# mainboard.net
KiCad netlist of a schematic drawn in EAGLE
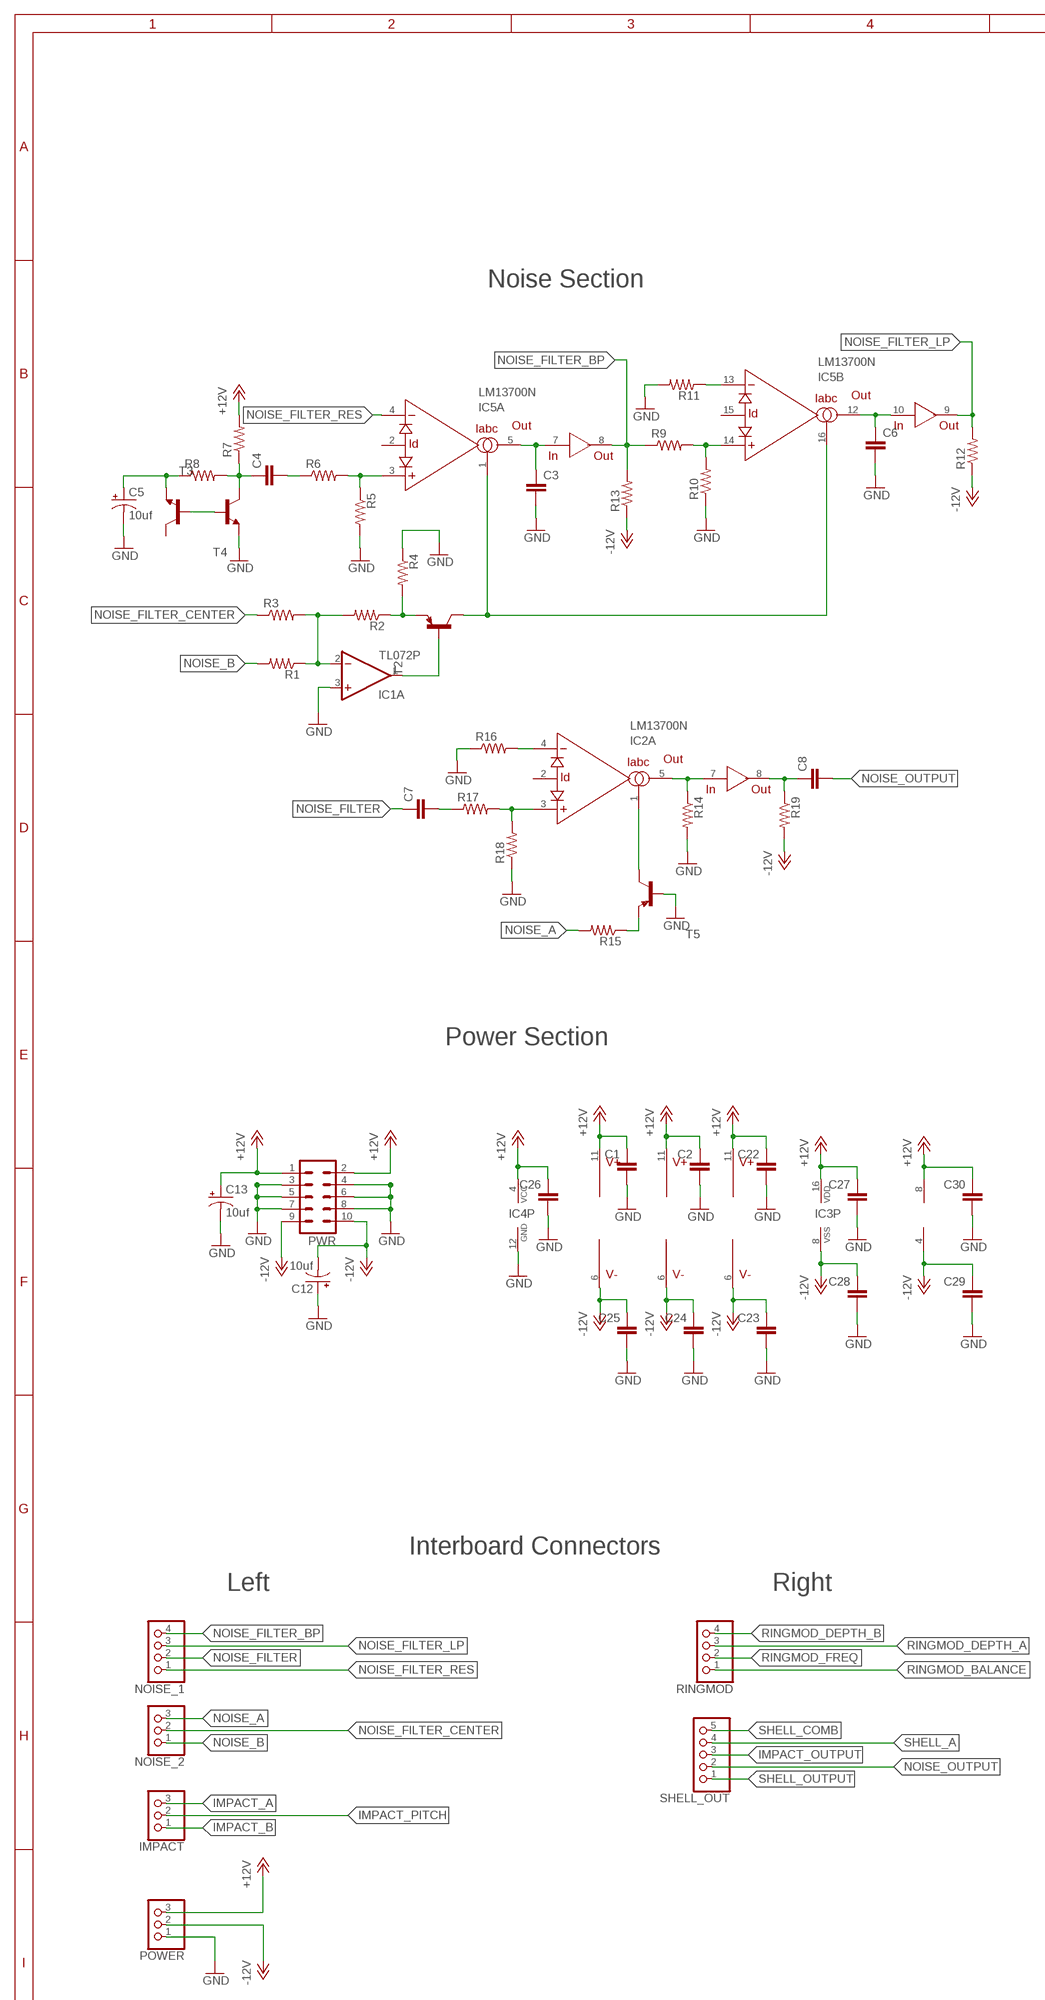
[diagram p0: schematic, sheet 1, part 1 of 2]
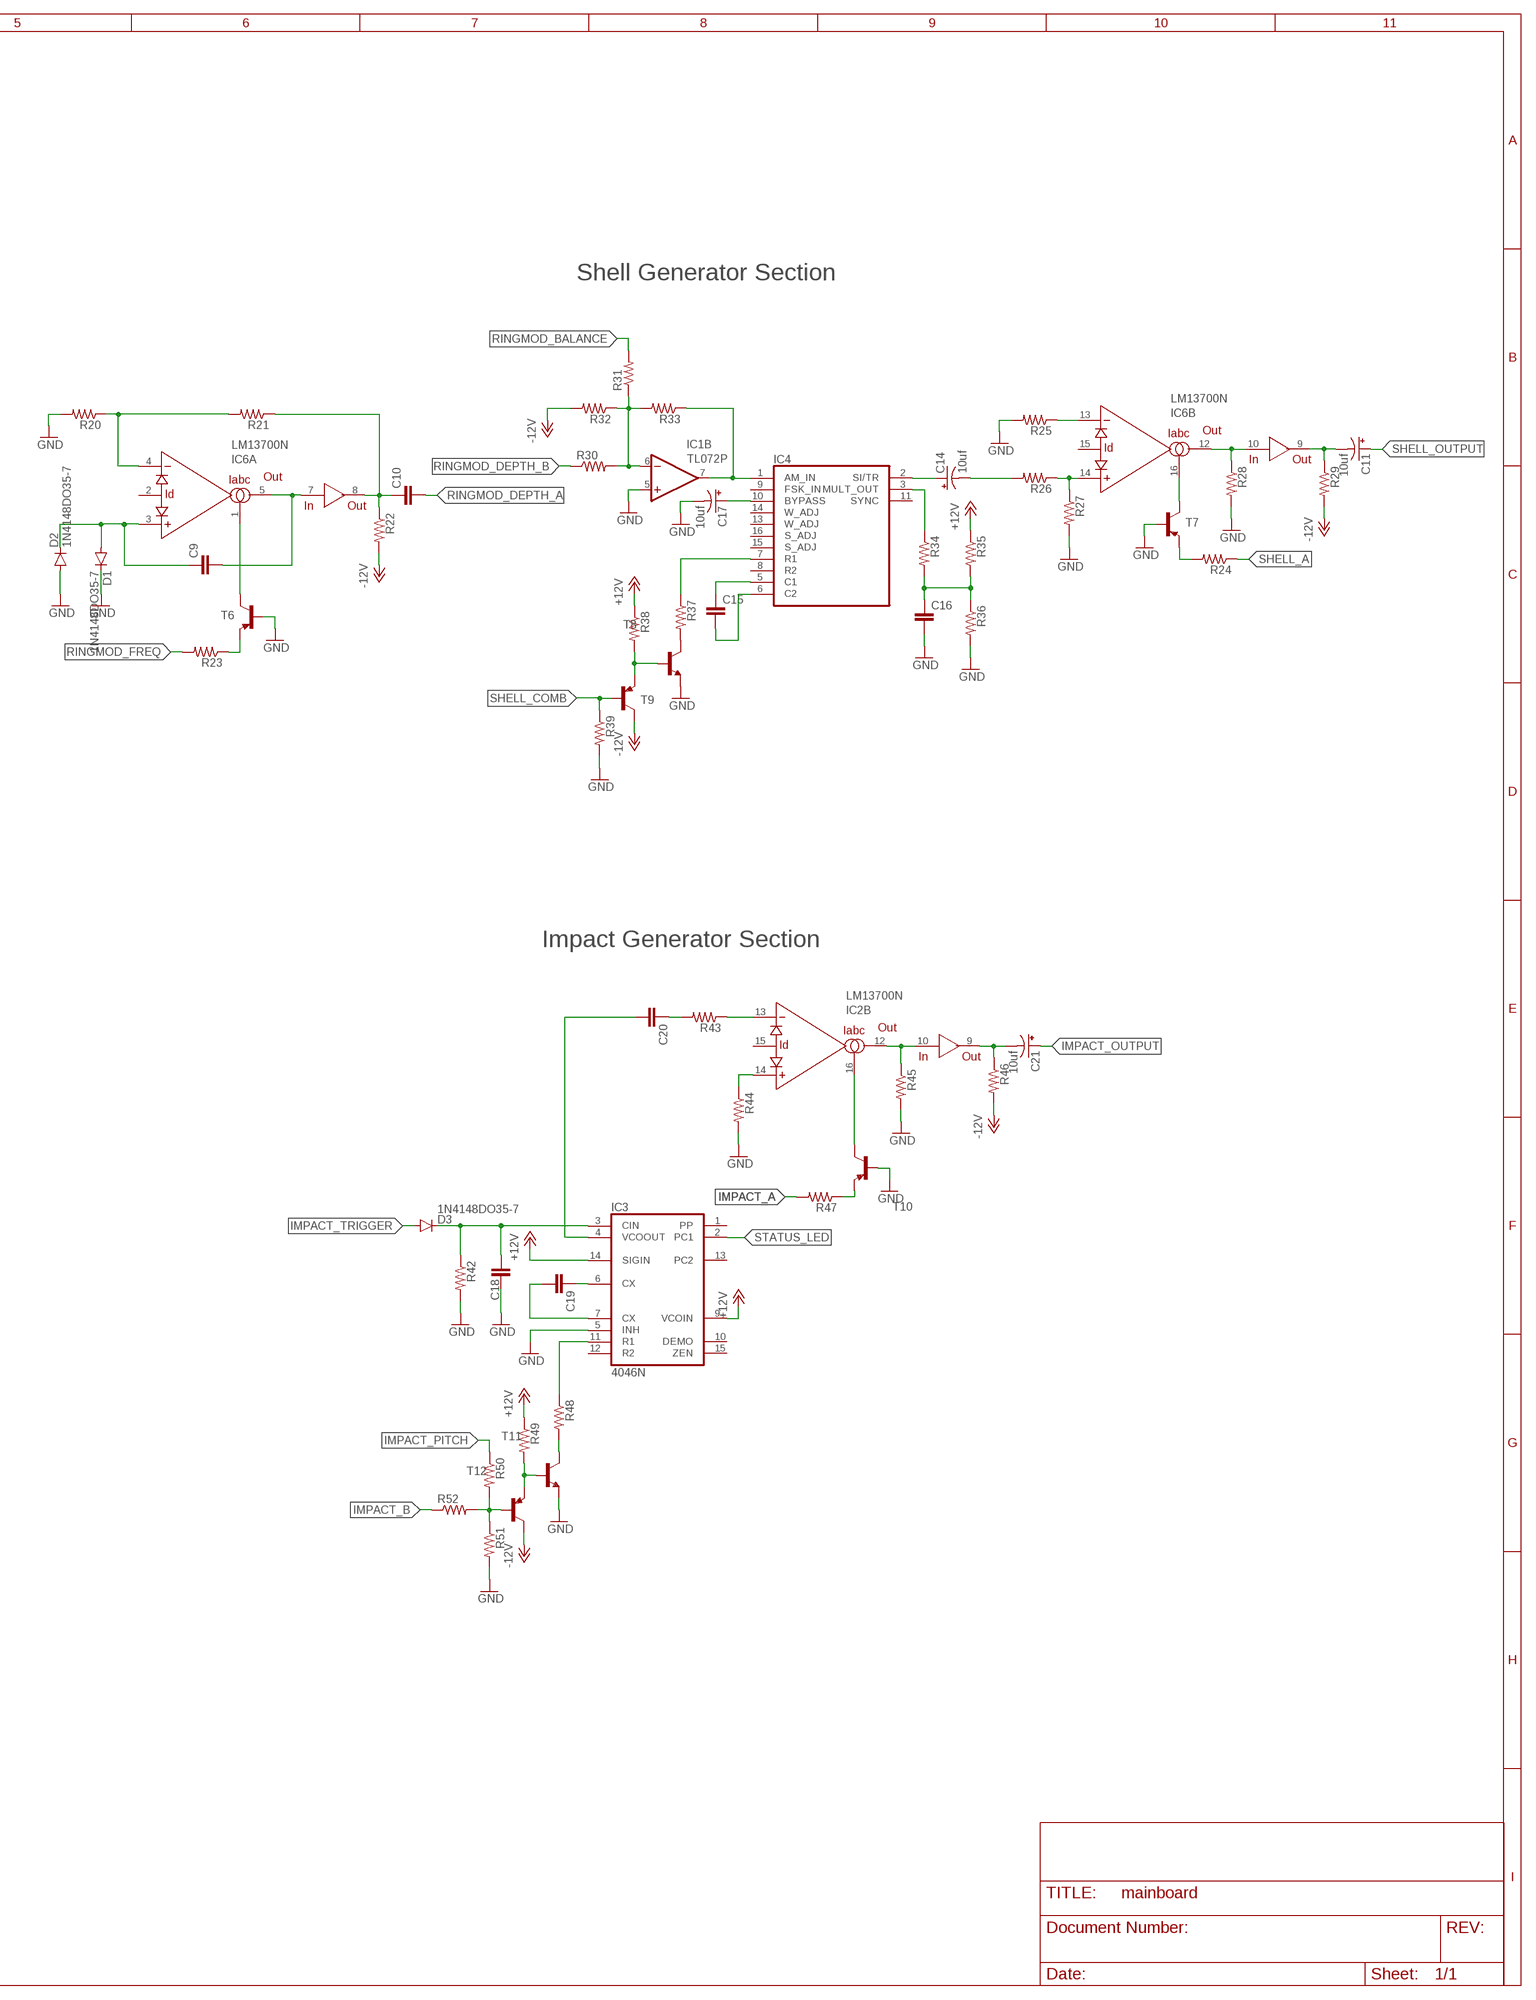
[diagram p1: schematic, sheet 1, part 2 of 2]

(export (version "E")
  (design (tool "Eeschema 10.0.6"))
  (components
    (comp (ref "C1")
      (value "C-EU050-024X044")
      (footprint "eagle-import:C050-024X044")
      (libsource (lib "eagle-import") (part "C-EU050-024X044"))
    )
    (comp (ref "C2")
      (value "C-EU050-024X044")
      (footprint "eagle-import:C050-024X044")
      (libsource (lib "eagle-import") (part "C-EU050-024X044"))
    )
    (comp (ref "C3")
      (value "C-EU050-024X044")
      (footprint "eagle-import:C050-024X044")
      (libsource (lib "eagle-import") (part "C-EU050-024X044"))
    )
    (comp (ref "C4")
      (value "C-EU050-024X044")
      (footprint "eagle-import:C050-024X044")
      (libsource (lib "eagle-import") (part "C-EU050-024X044"))
    )
    (comp (ref "C5")
      (value "10uf")
      (footprint "eagle-import:E2,5-5")
      (libsource (lib "eagle-import") (part "CPOL-USE2.5-5"))
    )
    (comp (ref "C6")
      (value "C-EU050-024X044")
      (footprint "eagle-import:C050-024X044")
      (libsource (lib "eagle-import") (part "C-EU050-024X044"))
    )
    (comp (ref "C7")
      (value "C-EU050-024X044")
      (footprint "eagle-import:C050-024X044")
      (libsource (lib "eagle-import") (part "C-EU050-024X044"))
    )
    (comp (ref "C8")
      (value "C-EU050-024X044")
      (footprint "eagle-import:C050-024X044")
      (libsource (lib "eagle-import") (part "C-EU050-024X044"))
    )
    (comp (ref "C9")
      (value "C-EU050-024X044")
      (footprint "eagle-import:C050-024X044")
      (libsource (lib "eagle-import") (part "C-EU050-024X044"))
    )
    (comp (ref "C10")
      (value "C-EU050-024X044")
      (footprint "eagle-import:C050-024X044")
      (libsource (lib "eagle-import") (part "C-EU050-024X044"))
    )
    (comp (ref "C11")
      (value "10uf")
      (footprint "eagle-import:E2,5-5")
      (libsource (lib "eagle-import") (part "CPOL-USE2.5-5"))
    )
    (comp (ref "C12")
      (value "10uf")
      (footprint "eagle-import:E2,5-5")
      (libsource (lib "eagle-import") (part "CPOL-USE2.5-5"))
    )
    (comp (ref "C13")
      (value "10uf")
      (footprint "eagle-import:E2,5-5")
      (libsource (lib "eagle-import") (part "CPOL-USE2.5-5"))
    )
    (comp (ref "C14")
      (value "10uf")
      (footprint "eagle-import:E2,5-5")
      (libsource (lib "eagle-import") (part "CPOL-USE2.5-5"))
    )
    (comp (ref "C15")
      (value "C-EU050-024X044")
      (footprint "eagle-import:C050-024X044")
      (libsource (lib "eagle-import") (part "C-EU050-024X044"))
    )
    (comp (ref "C16")
      (value "C-EU050-024X044")
      (footprint "eagle-import:C050-024X044")
      (libsource (lib "eagle-import") (part "C-EU050-024X044"))
    )
    (comp (ref "C17")
      (value "10uf")
      (footprint "eagle-import:E2,5-5")
      (libsource (lib "eagle-import") (part "CPOL-USE2.5-5"))
    )
    (comp (ref "C18")
      (value "C-EU050-024X044")
      (footprint "eagle-import:C050-024X044")
      (libsource (lib "eagle-import") (part "C-EU050-024X044"))
    )
    (comp (ref "C19")
      (value "C-EU050-024X044")
      (footprint "eagle-import:C050-024X044")
      (libsource (lib "eagle-import") (part "C-EU050-024X044"))
    )
    (comp (ref "C20")
      (value "C-EU050-024X044")
      (footprint "eagle-import:C050-024X044")
      (libsource (lib "eagle-import") (part "C-EU050-024X044"))
    )
    (comp (ref "C21")
      (value "10uf")
      (footprint "eagle-import:E2,5-5")
      (libsource (lib "eagle-import") (part "CPOL-USE2.5-5"))
    )
    (comp (ref "C22")
      (value "C-EU050-024X044")
      (footprint "eagle-import:C050-024X044")
      (libsource (lib "eagle-import") (part "C-EU050-024X044"))
    )
    (comp (ref "C23")
      (value "C-EU050-024X044")
      (footprint "eagle-import:C050-024X044")
      (libsource (lib "eagle-import") (part "C-EU050-024X044"))
    )
    (comp (ref "C24")
      (value "C-EU050-024X044")
      (footprint "eagle-import:C050-024X044")
      (libsource (lib "eagle-import") (part "C-EU050-024X044"))
    )
    (comp (ref "C25")
      (value "C-EU050-024X044")
      (footprint "eagle-import:C050-024X044")
      (libsource (lib "eagle-import") (part "C-EU050-024X044"))
    )
    (comp (ref "C26")
      (value "C-EU050-024X044")
      (footprint "eagle-import:C050-024X044")
      (libsource (lib "eagle-import") (part "C-EU050-024X044"))
    )
    (comp (ref "C27")
      (value "C-EU050-024X044")
      (footprint "eagle-import:C050-024X044")
      (libsource (lib "eagle-import") (part "C-EU050-024X044"))
    )
    (comp (ref "C28")
      (value "C-EU050-024X044")
      (footprint "eagle-import:C050-024X044")
      (libsource (lib "eagle-import") (part "C-EU050-024X044"))
    )
    (comp (ref "C29")
      (value "C-EU050-024X044")
      (footprint "eagle-import:C050-024X044")
      (libsource (lib "eagle-import") (part "C-EU050-024X044"))
    )
    (comp (ref "C30")
      (value "C-EU050-024X044")
      (footprint "eagle-import:C050-024X044")
      (libsource (lib "eagle-import") (part "C-EU050-024X044"))
    )
    (comp (ref "D1")
      (value "1N4148DO35-7")
      (footprint "eagle-import:DO35-7")
      (libsource (lib "eagle-import") (part "1N4148DO35-7"))
    )
    (comp (ref "D2")
      (value "1N4148DO35-7")
      (footprint "eagle-import:DO35-7")
      (libsource (lib "eagle-import") (part "1N4148DO35-7"))
    )
    (comp (ref "D3")
      (value "1N4148DO35-7")
      (footprint "eagle-import:DO35-7")
      (libsource (lib "eagle-import") (part "1N4148DO35-7"))
    )
    (comp (ref "IC1")
      (value "TL072P")
      (footprint "eagle-import:DIL08")
      (libsource (lib "eagle-import") (part "TL072P"))
    )
    (comp (ref "IC2")
      (value "LM13700N")
      (footprint "eagle-import:DIL16")
      (libsource (lib "eagle-import") (part "LM13700N"))
    )
    (comp (ref "IC3")
      (value "4046N")
      (footprint "eagle-import:DIL16")
      (libsource (lib "eagle-import") (part "4046N"))
    )
    (comp (ref "IC4")
      (value "XR-2206")
      (footprint "eagle-import:DIL16")
      (libsource (lib "eagle-import") (part "XR-2206"))
    )
    (comp (ref "IC5")
      (value "LM13700N")
      (footprint "eagle-import:DIL16")
      (libsource (lib "eagle-import") (part "LM13700N"))
    )
    (comp (ref "IC6")
      (value "LM13700N")
      (footprint "eagle-import:DIL16")
      (libsource (lib "eagle-import") (part "LM13700N"))
    )
    (comp (ref "IMPACT")
      (value "PINHD-1X3")
      (footprint "eagle-import:1X03")
      (libsource (lib "eagle-import") (part "PINHD-1X3"))
    )
    (comp (ref "NOISE_1")
      (value "PINHD-1X4")
      (footprint "eagle-import:1X04")
      (libsource (lib "eagle-import") (part "PINHD-1X4"))
    )
    (comp (ref "NOISE_2")
      (value "PINHD-1X3")
      (footprint "eagle-import:1X03")
      (libsource (lib "eagle-import") (part "PINHD-1X3"))
    )
    (comp (ref "POWER")
      (value "PINHD-1X3")
      (footprint "eagle-import:1X03")
      (libsource (lib "eagle-import") (part "PINHD-1X3"))
    )
    (comp (ref "PWR")
      (value "ML10")
      (footprint "eagle-import:ML10")
      (libsource (lib "eagle-import") (part "ML10"))
    )
    (comp (ref "R1")
      (value "R-US_0207/7")
      (footprint "eagle-import:0207_7")
      (libsource (lib "eagle-import") (part "R-US_0207/7"))
    )
    (comp (ref "R2")
      (value "R-US_0207/7")
      (footprint "eagle-import:0207_7")
      (libsource (lib "eagle-import") (part "R-US_0207/7"))
    )
    (comp (ref "R3")
      (value "R-US_0207/7")
      (footprint "eagle-import:0207_7")
      (libsource (lib "eagle-import") (part "R-US_0207/7"))
    )
    (comp (ref "R4")
      (value "R-US_0207/7")
      (footprint "eagle-import:0207_7")
      (libsource (lib "eagle-import") (part "R-US_0207/7"))
    )
    (comp (ref "R5")
      (value "R-US_0207/7")
      (footprint "eagle-import:0207_7")
      (libsource (lib "eagle-import") (part "R-US_0207/7"))
    )
    (comp (ref "R6")
      (value "R-US_0207/7")
      (footprint "eagle-import:0207_7")
      (libsource (lib "eagle-import") (part "R-US_0207/7"))
    )
    (comp (ref "R7")
      (value "R-US_0207/7")
      (footprint "eagle-import:0207_7")
      (libsource (lib "eagle-import") (part "R-US_0207/7"))
    )
    (comp (ref "R8")
      (value "R-US_0207/7")
      (footprint "eagle-import:0207_7")
      (libsource (lib "eagle-import") (part "R-US_0207/7"))
    )
    (comp (ref "R9")
      (value "R-US_0207/7")
      (footprint "eagle-import:0207_7")
      (libsource (lib "eagle-import") (part "R-US_0207/7"))
    )
    (comp (ref "R10")
      (value "R-US_0207/7")
      (footprint "eagle-import:0207_7")
      (libsource (lib "eagle-import") (part "R-US_0207/7"))
    )
    (comp (ref "R11")
      (value "R-US_0207/7")
      (footprint "eagle-import:0207_7")
      (libsource (lib "eagle-import") (part "R-US_0207/7"))
    )
    (comp (ref "R12")
      (value "R-US_0207/7")
      (footprint "eagle-import:0207_7")
      (libsource (lib "eagle-import") (part "R-US_0207/7"))
    )
    (comp (ref "R13")
      (value "R-US_0207/7")
      (footprint "eagle-import:0207_7")
      (libsource (lib "eagle-import") (part "R-US_0207/7"))
    )
    (comp (ref "R14")
      (value "R-US_0207/7")
      (footprint "eagle-import:0207_7")
      (libsource (lib "eagle-import") (part "R-US_0207/7"))
    )
    (comp (ref "R15")
      (value "R-US_0207/7")
      (footprint "eagle-import:0207_7")
      (libsource (lib "eagle-import") (part "R-US_0207/7"))
    )
    (comp (ref "R16")
      (value "R-US_0207/7")
      (footprint "eagle-import:0207_7")
      (libsource (lib "eagle-import") (part "R-US_0207/7"))
    )
    (comp (ref "R17")
      (value "R-US_0207/7")
      (footprint "eagle-import:0207_7")
      (libsource (lib "eagle-import") (part "R-US_0207/7"))
    )
    (comp (ref "R18")
      (value "R-US_0207/7")
      (footprint "eagle-import:0207_7")
      (libsource (lib "eagle-import") (part "R-US_0207/7"))
    )
    (comp (ref "R19")
      (value "R-US_0207/7")
      (footprint "eagle-import:0207_7")
      (libsource (lib "eagle-import") (part "R-US_0207/7"))
    )
    (comp (ref "R20")
      (value "R-US_0207/7")
      (footprint "eagle-import:0207_7")
      (libsource (lib "eagle-import") (part "R-US_0207/7"))
    )
    (comp (ref "R21")
      (value "R-US_0207/7")
      (footprint "eagle-import:0207_7")
      (libsource (lib "eagle-import") (part "R-US_0207/7"))
    )
    (comp (ref "R22")
      (value "R-US_0207/7")
      (footprint "eagle-import:0207_7")
      (libsource (lib "eagle-import") (part "R-US_0207/7"))
    )
    (comp (ref "R23")
      (value "R-US_0207/7")
      (footprint "eagle-import:0207_7")
      (libsource (lib "eagle-import") (part "R-US_0207/7"))
    )
    (comp (ref "R24")
      (value "R-US_0207/7")
      (footprint "eagle-import:0207_7")
      (libsource (lib "eagle-import") (part "R-US_0207/7"))
    )
    (comp (ref "R25")
      (value "R-US_0207/7")
      (footprint "eagle-import:0207_7")
      (libsource (lib "eagle-import") (part "R-US_0207/7"))
    )
    (comp (ref "R26")
      (value "R-US_0207/7")
      (footprint "eagle-import:0207_7")
      (libsource (lib "eagle-import") (part "R-US_0207/7"))
    )
    (comp (ref "R27")
      (value "R-US_0207/7")
      (footprint "eagle-import:0207_7")
      (libsource (lib "eagle-import") (part "R-US_0207/7"))
    )
    (comp (ref "R28")
      (value "R-US_0207/7")
      (footprint "eagle-import:0207_7")
      (libsource (lib "eagle-import") (part "R-US_0207/7"))
    )
    (comp (ref "R29")
      (value "R-US_0207/7")
      (footprint "eagle-import:0207_7")
      (libsource (lib "eagle-import") (part "R-US_0207/7"))
    )
    (comp (ref "R30")
      (value "R-US_0207/7")
      (footprint "eagle-import:0207_7")
      (libsource (lib "eagle-import") (part "R-US_0207/7"))
    )
    (comp (ref "R31")
      (value "R-US_0207/7")
      (footprint "eagle-import:0207_7")
      (libsource (lib "eagle-import") (part "R-US_0207/7"))
    )
    (comp (ref "R32")
      (value "R-US_0207/7")
      (footprint "eagle-import:0207_7")
      (libsource (lib "eagle-import") (part "R-US_0207/7"))
    )
    (comp (ref "R33")
      (value "R-US_0207/7")
      (footprint "eagle-import:0207_7")
      (libsource (lib "eagle-import") (part "R-US_0207/7"))
    )
    (comp (ref "R34")
      (value "R-US_0207/7")
      (footprint "eagle-import:0207_7")
      (libsource (lib "eagle-import") (part "R-US_0207/7"))
    )
    (comp (ref "R35")
      (value "R-US_0207/7")
      (footprint "eagle-import:0207_7")
      (libsource (lib "eagle-import") (part "R-US_0207/7"))
    )
    (comp (ref "R36")
      (value "R-US_0207/7")
      (footprint "eagle-import:0207_7")
      (libsource (lib "eagle-import") (part "R-US_0207/7"))
    )
    (comp (ref "R37")
      (value "R-US_0207/7")
      (footprint "eagle-import:0207_7")
      (libsource (lib "eagle-import") (part "R-US_0207/7"))
    )
    (comp (ref "R38")
      (value "R-US_0207/7")
      (footprint "eagle-import:0207_7")
      (libsource (lib "eagle-import") (part "R-US_0207/7"))
    )
    (comp (ref "R39")
      (value "R-US_0207/7")
      (footprint "eagle-import:0207_7")
      (libsource (lib "eagle-import") (part "R-US_0207/7"))
    )
    (comp (ref "R42")
      (value "R-US_0207/7")
      (footprint "eagle-import:0207_7")
      (libsource (lib "eagle-import") (part "R-US_0207/7"))
    )
    (comp (ref "R43")
      (value "R-US_0207/7")
      (footprint "eagle-import:0207_7")
      (libsource (lib "eagle-import") (part "R-US_0207/7"))
    )
    (comp (ref "R44")
      (value "R-US_0207/7")
      (footprint "eagle-import:0207_7")
      (libsource (lib "eagle-import") (part "R-US_0207/7"))
    )
    (comp (ref "R45")
      (value "R-US_0207/7")
      (footprint "eagle-import:0207_7")
      (libsource (lib "eagle-import") (part "R-US_0207/7"))
    )
    (comp (ref "R46")
      (value "R-US_0207/7")
      (footprint "eagle-import:0207_7")
      (libsource (lib "eagle-import") (part "R-US_0207/7"))
    )
    (comp (ref "R47")
      (value "R-US_0207/7")
      (footprint "eagle-import:0207_7")
      (libsource (lib "eagle-import") (part "R-US_0207/7"))
    )
    (comp (ref "R48")
      (value "R-US_0207/7")
      (footprint "eagle-import:0207_7")
      (libsource (lib "eagle-import") (part "R-US_0207/7"))
    )
    (comp (ref "R49")
      (value "R-US_0207/7")
      (footprint "eagle-import:0207_7")
      (libsource (lib "eagle-import") (part "R-US_0207/7"))
    )
    (comp (ref "R50")
      (value "R-US_0207/7")
      (footprint "eagle-import:0207_7")
      (libsource (lib "eagle-import") (part "R-US_0207/7"))
    )
    (comp (ref "R51")
      (value "R-US_0207/7")
      (footprint "eagle-import:0207_7")
      (libsource (lib "eagle-import") (part "R-US_0207/7"))
    )
    (comp (ref "R52")
      (value "R-US_0207/7")
      (footprint "eagle-import:0207_7")
      (libsource (lib "eagle-import") (part "R-US_0207/7"))
    )
    (comp (ref "RINGMOD")
      (value "PINHD-1X4")
      (footprint "eagle-import:1X04")
      (libsource (lib "eagle-import") (part "PINHD-1X4"))
    )
    (comp (ref "SHELL_OUT")
      (value "PINHD-1X5")
      (footprint "eagle-import:1X05")
      (libsource (lib "eagle-import") (part "PINHD-1X5"))
    )
    (comp (ref "T2")
      (value "2N3906-PNP-TO92-EBC")
      (footprint "eagle-import:TO92-EBC")
      (libsource (lib "eagle-import") (part "-PNP-TO92-EBC2N3906"))
    )
    (comp (ref "T3")
      (value "2N3904-NPN-TO92-EBC")
      (footprint "eagle-import:TO92-EBC")
      (libsource (lib "eagle-import") (part "-NPN-TO92-EBC2N3904"))
    )
    (comp (ref "T4")
      (value "2N3904-NPN-TO92-EBC")
      (footprint "eagle-import:TO92-EBC")
      (libsource (lib "eagle-import") (part "-NPN-TO92-EBC2N3904"))
    )
    (comp (ref "T5")
      (value "2N3906-PNP-TO92-EBC")
      (footprint "eagle-import:TO92-EBC")
      (libsource (lib "eagle-import") (part "-PNP-TO92-EBC2N3906"))
    )
    (comp (ref "T6")
      (value "2N3906-PNP-TO92-EBC")
      (footprint "eagle-import:TO92-EBC")
      (libsource (lib "eagle-import") (part "-PNP-TO92-EBC2N3906"))
    )
    (comp (ref "T7")
      (value "2N3906-PNP-TO92-EBC")
      (footprint "eagle-import:TO92-EBC")
      (libsource (lib "eagle-import") (part "-PNP-TO92-EBC2N3906"))
    )
    (comp (ref "T8")
      (value "2N3904-NPN-TO92-EBC")
      (footprint "eagle-import:TO92-EBC")
      (libsource (lib "eagle-import") (part "-NPN-TO92-EBC2N3904"))
    )
    (comp (ref "T9")
      (value "2N3906-PNP-TO92-EBC")
      (footprint "eagle-import:TO92-EBC")
      (libsource (lib "eagle-import") (part "-PNP-TO92-EBC2N3906"))
    )
    (comp (ref "T10")
      (value "2N3906-PNP-TO92-EBC")
      (footprint "eagle-import:TO92-EBC")
      (libsource (lib "eagle-import") (part "-PNP-TO92-EBC2N3906"))
    )
    (comp (ref "T11")
      (value "2N3904-NPN-TO92-EBC")
      (footprint "eagle-import:TO92-EBC")
      (libsource (lib "eagle-import") (part "-NPN-TO92-EBC2N3904"))
    )
    (comp (ref "T12")
      (value "2N3906-PNP-TO92-EBC")
      (footprint "eagle-import:TO92-EBC")
      (libsource (lib "eagle-import") (part "-PNP-TO92-EBC2N3906"))
    )
  )
  (nets
    (net (code "1") (name "+12V") (class "Default")
      (node (ref "C1") (pin "1") (pinfunction "1_1") (pintype "passive"))
      (node (ref "C13") (pin "+") (pinfunction "+_+") (pintype "passive"))
      (node (ref "C2") (pin "1") (pinfunction "1_1") (pintype "passive"))
      (node (ref "C22") (pin "1") (pinfunction "1_1") (pintype "passive"))
      (node (ref "C26") (pin "1") (pinfunction "1_1") (pintype "passive"))
      (node (ref "C27") (pin "1") (pinfunction "1_1") (pintype "passive"))
      (node (ref "C30") (pin "1") (pinfunction "1_1") (pintype "passive"))
      (node (ref "IC1") (pin "8") (pinfunction "V+_8") (pintype "power_in"))
      (node (ref "IC2") (pin "11") (pinfunction "V+_11") (pintype "bidirectional"))
      (node (ref "IC3") (pin "14") (pinfunction "SIGIN_14") (pintype "input"))
      (node (ref "IC3") (pin "16") (pinfunction "VDD_16") (pintype "power_in"))
      (node (ref "IC3") (pin "9") (pinfunction "VCOIN_9") (pintype "input"))
      (node (ref "IC4") (pin "4") (pinfunction "VCC_4") (pintype "power_in"))
      (node (ref "IC5") (pin "11") (pinfunction "V+_11") (pintype "bidirectional"))
      (node (ref "IC6") (pin "11") (pinfunction "V+_11") (pintype "bidirectional"))
      (node (ref "POWER") (pin "3") (pinfunction "3_3") (pintype "passive"))
      (node (ref "PWR") (pin "1") (pinfunction "1_1") (pintype "passive"))
      (node (ref "PWR") (pin "2") (pinfunction "2_2") (pintype "passive"))
      (node (ref "R35") (pin "1") (pinfunction "1_1") (pintype "passive"))
      (node (ref "R38") (pin "1") (pinfunction "1_1") (pintype "passive"))
      (node (ref "R49") (pin "1") (pinfunction "1_1") (pintype "passive"))
      (node (ref "R7") (pin "2") (pinfunction "2_2") (pintype "passive"))
    )
    (net (code "2") (name "-12V") (class "Default")
      (node (ref "C12") (pin "-") (pinfunction "-_-") (pintype "passive"))
      (node (ref "C23") (pin "1") (pinfunction "1_1") (pintype "passive"))
      (node (ref "C24") (pin "1") (pinfunction "1_1") (pintype "passive"))
      (node (ref "C25") (pin "1") (pinfunction "1_1") (pintype "passive"))
      (node (ref "C28") (pin "1") (pinfunction "1_1") (pintype "passive"))
      (node (ref "C29") (pin "1") (pinfunction "1_1") (pintype "passive"))
      (node (ref "IC1") (pin "4") (pinfunction "V-_4") (pintype "power_in"))
      (node (ref "IC2") (pin "6") (pinfunction "V-_6") (pintype "bidirectional"))
      (node (ref "IC3") (pin "8") (pinfunction "VSS_8") (pintype "power_in"))
      (node (ref "IC5") (pin "6") (pinfunction "V-_6") (pintype "bidirectional"))
      (node (ref "IC6") (pin "6") (pinfunction "V-_6") (pintype "bidirectional"))
      (node (ref "POWER") (pin "2") (pinfunction "2_2") (pintype "passive"))
      (node (ref "PWR") (pin "10") (pinfunction "10_10") (pintype "passive"))
      (node (ref "PWR") (pin "9") (pinfunction "9_9") (pintype "passive"))
      (node (ref "R12") (pin "1") (pinfunction "1_1") (pintype "passive"))
      (node (ref "R13") (pin "1") (pinfunction "1_1") (pintype "passive"))
      (node (ref "R19") (pin "2") (pinfunction "2_2") (pintype "passive"))
      (node (ref "R22") (pin "2") (pinfunction "2_2") (pintype "passive"))
      (node (ref "R29") (pin "2") (pinfunction "2_2") (pintype "passive"))
      (node (ref "R32") (pin "2") (pinfunction "2_2") (pintype "passive"))
      (node (ref "R46") (pin "2") (pinfunction "2_2") (pintype "passive"))
      (node (ref "T12") (pin "C") (pinfunction "C_C") (pintype "passive"))
      (node (ref "T9") (pin "C") (pinfunction "C_C") (pintype "passive"))
    )
    (net (code "3") (name "GND") (class "Default")
      (node (ref "C1") (pin "2") (pinfunction "2_2") (pintype "passive"))
      (node (ref "C12") (pin "+") (pinfunction "+_+") (pintype "passive"))
      (node (ref "C13") (pin "-") (pinfunction "-_-") (pintype "passive"))
      (node (ref "C16") (pin "2") (pinfunction "2_2") (pintype "passive"))
      (node (ref "C17") (pin "-") (pinfunction "-_-") (pintype "passive"))
      (node (ref "C18") (pin "1") (pinfunction "1_1") (pintype "passive"))
      (node (ref "C2") (pin "2") (pinfunction "2_2") (pintype "passive"))
      (node (ref "C22") (pin "2") (pinfunction "2_2") (pintype "passive"))
      (node (ref "C23") (pin "2") (pinfunction "2_2") (pintype "passive"))
      (node (ref "C24") (pin "2") (pinfunction "2_2") (pintype "passive"))
      (node (ref "C25") (pin "2") (pinfunction "2_2") (pintype "passive"))
      (node (ref "C26") (pin "2") (pinfunction "2_2") (pintype "passive"))
      (node (ref "C27") (pin "2") (pinfunction "2_2") (pintype "passive"))
      (node (ref "C28") (pin "2") (pinfunction "2_2") (pintype "passive"))
      (node (ref "C29") (pin "2") (pinfunction "2_2") (pintype "passive"))
      (node (ref "C3") (pin "2") (pinfunction "2_2") (pintype "passive"))
      (node (ref "C30") (pin "2") (pinfunction "2_2") (pintype "passive"))
      (node (ref "C5") (pin "-") (pinfunction "-_-") (pintype "passive"))
      (node (ref "C6") (pin "2") (pinfunction "2_2") (pintype "passive"))
      (node (ref "D1") (pin "C") (pinfunction "C_C") (pintype "passive"))
      (node (ref "D2") (pin "A") (pinfunction "A_A") (pintype "passive"))
      (node (ref "IC1") (pin "3") (pinfunction "+IN_3") (pintype "input"))
      (node (ref "IC1") (pin "5") (pinfunction "+IN_5") (pintype "input"))
      (node (ref "IC3") (pin "5") (pinfunction "INH_5") (pintype "input"))
      (node (ref "IC4") (pin "12") (pinfunction "GND_12") (pintype "power_in"))
      (node (ref "POWER") (pin "1") (pinfunction "1_1") (pintype "passive"))
      (node (ref "PWR") (pin "3") (pinfunction "3_3") (pintype "passive"))
      (node (ref "PWR") (pin "4") (pinfunction "4_4") (pintype "passive"))
      (node (ref "PWR") (pin "5") (pinfunction "5_5") (pintype "passive"))
      (node (ref "PWR") (pin "6") (pinfunction "6_6") (pintype "passive"))
      (node (ref "PWR") (pin "7") (pinfunction "7_7") (pintype "passive"))
      (node (ref "PWR") (pin "8") (pinfunction "8_8") (pintype "passive"))
      (node (ref "R10") (pin "1") (pinfunction "1_1") (pintype "passive"))
      (node (ref "R11") (pin "2") (pinfunction "2_2") (pintype "passive"))
      (node (ref "R14") (pin "2") (pinfunction "2_2") (pintype "passive"))
      (node (ref "R16") (pin "1") (pinfunction "1_1") (pintype "passive"))
      (node (ref "R18") (pin "1") (pinfunction "1_1") (pintype "passive"))
      (node (ref "R20") (pin "2") (pinfunction "2_2") (pintype "passive"))
      (node (ref "R25") (pin "2") (pinfunction "2_2") (pintype "passive"))
      (node (ref "R27") (pin "2") (pinfunction "2_2") (pintype "passive"))
      (node (ref "R28") (pin "2") (pinfunction "2_2") (pintype "passive"))
      (node (ref "R36") (pin "2") (pinfunction "2_2") (pintype "passive"))
      (node (ref "R39") (pin "2") (pinfunction "2_2") (pintype "passive"))
      (node (ref "R4") (pin "1") (pinfunction "1_1") (pintype "passive"))
      (node (ref "R42") (pin "2") (pinfunction "2_2") (pintype "passive"))
      (node (ref "R44") (pin "2") (pinfunction "2_2") (pintype "passive"))
      (node (ref "R45") (pin "2") (pinfunction "2_2") (pintype "passive"))
      (node (ref "R5") (pin "2") (pinfunction "2_2") (pintype "passive"))
      (node (ref "R51") (pin "2") (pinfunction "2_2") (pintype "passive"))
      (node (ref "T10") (pin "B") (pinfunction "B_B") (pintype "passive"))
      (node (ref "T11") (pin "E") (pinfunction "E_E") (pintype "passive"))
      (node (ref "T3") (pin "E") (pinfunction "E_E") (pintype "passive"))
      (node (ref "T5") (pin "B") (pinfunction "B_B") (pintype "passive"))
      (node (ref "T6") (pin "B") (pinfunction "B_B") (pintype "passive"))
      (node (ref "T7") (pin "B") (pinfunction "B_B") (pintype "passive"))
      (node (ref "T8") (pin "E") (pinfunction "E_E") (pintype "passive"))
    )
    (net (code "4") (name "IMPACT_A") (class "Default")
      (node (ref "IMPACT") (pin "3") (pinfunction "3_3") (pintype "passive"))
      (node (ref "R47") (pin "2") (pinfunction "2_2") (pintype "passive"))
    )
    (net (code "5") (name "IMPACT_B") (class "Default")
      (node (ref "IMPACT") (pin "1") (pinfunction "1_1") (pintype "passive"))
      (node (ref "R52") (pin "1") (pinfunction "1_1") (pintype "passive"))
    )
    (net (code "6") (name "IMPACT_OUTPUT") (class "Default")
      (node (ref "C21") (pin "+") (pinfunction "+_+") (pintype "passive"))
      (node (ref "SHELL_OUT") (pin "3") (pinfunction "3_3") (pintype "passive"))
    )
    (net (code "7") (name "IMPACT_PITCH") (class "Default")
      (node (ref "IMPACT") (pin "2") (pinfunction "2_2") (pintype "passive"))
      (node (ref "R50") (pin "1") (pinfunction "1_1") (pintype "passive"))
    )
    (net (code "8") (name "IMPACT_TRIGGER") (class "Default")
      (node (ref "D3") (pin "A") (pinfunction "A_A") (pintype "passive"))
    )
    (net (code "9") (name "NOISE_A") (class "Default")
      (node (ref "NOISE_2") (pin "3") (pinfunction "3_3") (pintype "passive"))
      (node (ref "R15") (pin "2") (pinfunction "2_2") (pintype "passive"))
    )
    (net (code "10") (name "NOISE_B") (class "Default")
      (node (ref "NOISE_2") (pin "1") (pinfunction "1_1") (pintype "passive"))
      (node (ref "R1") (pin "2") (pinfunction "2_2") (pintype "passive"))
    )
    (net (code "11") (name "NOISE_FILTER") (class "Default")
      (node (ref "C7") (pin "1") (pinfunction "1_1") (pintype "passive"))
      (node (ref "NOISE_1") (pin "2") (pinfunction "2_2") (pintype "passive"))
    )
    (net (code "12") (name "NOISE_FILTER_BP") (class "Default")
      (node (ref "IC5") (pin "8") (pinfunction "OUT_8") (pintype "bidirectional"))
      (node (ref "NOISE_1") (pin "4") (pinfunction "4_4") (pintype "passive"))
      (node (ref "R13") (pin "2") (pinfunction "2_2") (pintype "passive"))
      (node (ref "R9") (pin "1") (pinfunction "1_1") (pintype "passive"))
    )
    (net (code "13") (name "NOISE_FILTER_CENTER") (class "Default")
      (node (ref "NOISE_2") (pin "2") (pinfunction "2_2") (pintype "passive"))
      (node (ref "R3") (pin "1") (pinfunction "1_1") (pintype "passive"))
    )
    (net (code "14") (name "NOISE_FILTER_LP") (class "Default")
      (node (ref "IC5") (pin "9") (pinfunction "OUT_9") (pintype "bidirectional"))
      (node (ref "NOISE_1") (pin "3") (pinfunction "3_3") (pintype "passive"))
      (node (ref "R12") (pin "2") (pinfunction "2_2") (pintype "passive"))
    )
    (net (code "15") (name "NOISE_FILTER_RES") (class "Default")
      (node (ref "IC5") (pin "4") (pinfunction "-IN_4") (pintype "bidirectional"))
      (node (ref "NOISE_1") (pin "1") (pinfunction "1_1") (pintype "passive"))
    )
    (net (code "16") (name "NOISE_OUTPUT") (class "Default")
      (node (ref "C8") (pin "2") (pinfunction "2_2") (pintype "passive"))
      (node (ref "SHELL_OUT") (pin "2") (pinfunction "2_2") (pintype "passive"))
    )
    (net (code "17") (name "Net-(C4-Pad1)") (class "Default")
      (node (ref "C4") (pin "1") (pinfunction "1_1") (pintype "passive"))
      (node (ref "R7") (pin "1") (pinfunction "1_1") (pintype "passive"))
      (node (ref "R8") (pin "2") (pinfunction "2_2") (pintype "passive"))
      (node (ref "T3") (pin "C") (pinfunction "C_C") (pintype "passive"))
    )
    (net (code "18") (name "Net-(C4-Pad2)") (class "Default")
      (node (ref "C4") (pin "2") (pinfunction "2_2") (pintype "passive"))
      (node (ref "R6") (pin "1") (pinfunction "1_1") (pintype "passive"))
    )
    (net (code "19") (name "Net-(C5-Pad+)") (class "Default")
      (node (ref "C5") (pin "+") (pinfunction "+_+") (pintype "passive"))
      (node (ref "R8") (pin "1") (pinfunction "1_1") (pintype "passive"))
      (node (ref "T4") (pin "E") (pinfunction "E_E") (pintype "passive"))
    )
    (net (code "20") (name "Net-(C7-Pad2)") (class "Default")
      (node (ref "C7") (pin "2") (pinfunction "2_2") (pintype "passive"))
      (node (ref "R17") (pin "1") (pinfunction "1_1") (pintype "passive"))
    )
    (net (code "21") (name "Net-(C14-Pad-)") (class "Default")
      (node (ref "C14") (pin "-") (pinfunction "-_-") (pintype "passive"))
      (node (ref "R26") (pin "2") (pinfunction "2_2") (pintype "passive"))
    )
    (net (code "22") (name "Net-(C16-Pad1)") (class "Default")
      (node (ref "C16") (pin "1") (pinfunction "1_1") (pintype "passive"))
      (node (ref "R34") (pin "2") (pinfunction "2_2") (pintype "passive"))
      (node (ref "R35") (pin "2") (pinfunction "2_2") (pintype "passive"))
      (node (ref "R36") (pin "1") (pinfunction "1_1") (pintype "passive"))
    )
    (net (code "23") (name "Net-(C19-Pad1)") (class "Default")
      (node (ref "C19") (pin "1") (pinfunction "1_1") (pintype "passive"))
      (node (ref "IC3") (pin "6") (pinfunction "CX_6") (pintype "input"))
    )
    (net (code "24") (name "Net-(C19-Pad2)") (class "Default")
      (node (ref "C19") (pin "2") (pinfunction "2_2") (pintype "passive"))
      (node (ref "IC3") (pin "7") (pinfunction "CX_7") (pintype "input"))
    )
    (net (code "25") (name "Net-(C20-Pad1)") (class "Default")
      (node (ref "C20") (pin "1") (pinfunction "1_1") (pintype "passive"))
      (node (ref "R43") (pin "2") (pinfunction "2_2") (pintype "passive"))
    )
    (net (code "26") (name "Net-(IC1A--IN)") (class "Default")
      (node (ref "IC1") (pin "2") (pinfunction "-IN_2") (pintype "input"))
      (node (ref "R1") (pin "1") (pinfunction "1_1") (pintype "passive"))
      (node (ref "R2") (pin "2") (pinfunction "2_2") (pintype "passive"))
      (node (ref "R3") (pin "2") (pinfunction "2_2") (pintype "passive"))
    )
    (net (code "27") (name "Net-(IC1A-OUT)") (class "Default")
      (node (ref "IC1") (pin "1") (pinfunction "OUT_1") (pintype "output"))
      (node (ref "T2") (pin "B") (pinfunction "B_B") (pintype "passive"))
    )
    (net (code "28") (name "Net-(IC1B--IN)") (class "Default")
      (node (ref "IC1") (pin "6") (pinfunction "-IN_6") (pintype "input"))
      (node (ref "R30") (pin "2") (pinfunction "2_2") (pintype "passive"))
      (node (ref "R31") (pin "1") (pinfunction "1_1") (pintype "passive"))
      (node (ref "R32") (pin "1") (pinfunction "1_1") (pintype "passive"))
      (node (ref "R33") (pin "2") (pinfunction "2_2") (pintype "passive"))
    )
    (net (code "29") (name "Net-(IC1B-OUT)") (class "Default")
      (node (ref "IC1") (pin "7") (pinfunction "OUT_7") (pintype "output"))
      (node (ref "IC4") (pin "1") (pinfunction "AM_IN_1") (pintype "input"))
      (node (ref "R33") (pin "1") (pinfunction "1_1") (pintype "passive"))
    )
    (net (code "30") (name "Net-(IC2A-+IN)") (class "Default")
      (node (ref "IC2") (pin "3") (pinfunction "+IN_3") (pintype "bidirectional"))
      (node (ref "R17") (pin "2") (pinfunction "2_2") (pintype "passive"))
      (node (ref "R18") (pin "2") (pinfunction "2_2") (pintype "passive"))
    )
    (net (code "31") (name "Net-(IC2A--IN)") (class "Default")
      (node (ref "IC2") (pin "4") (pinfunction "-IN_4") (pintype "bidirectional"))
      (node (ref "R16") (pin "2") (pinfunction "2_2") (pintype "passive"))
    )
    (net (code "32") (name "Net-(IC2A-IABC)") (class "Default")
      (node (ref "IC2") (pin "1") (pinfunction "IABC_1") (pintype "bidirectional"))
      (node (ref "T5") (pin "C") (pinfunction "C_C") (pintype "passive"))
    )
    (net (code "33") (name "Net-(IC2A-OUT)") (class "Default")
      (node (ref "IC2") (pin "5") (pinfunction "OUT_5") (pintype "bidirectional"))
      (node (ref "IC2") (pin "7") (pinfunction "IN_7") (pintype "bidirectional"))
      (node (ref "R14") (pin "1") (pinfunction "1_1") (pintype "passive"))
    )
    (net (code "34") (name "Net-(IC2B-+IN)") (class "Default")
      (node (ref "IC2") (pin "14") (pinfunction "+IN_14") (pintype "bidirectional"))
      (node (ref "R44") (pin "1") (pinfunction "1_1") (pintype "passive"))
    )
    (net (code "35") (name "Net-(IC2B--IN)") (class "Default")
      (node (ref "IC2") (pin "13") (pinfunction "-IN_13") (pintype "bidirectional"))
      (node (ref "R43") (pin "1") (pinfunction "1_1") (pintype "passive"))
    )
    (net (code "36") (name "Net-(IC2B-IABC)") (class "Default")
      (node (ref "IC2") (pin "16") (pinfunction "IABC_16") (pintype "bidirectional"))
      (node (ref "T10") (pin "C") (pinfunction "C_C") (pintype "passive"))
    )
    (net (code "37") (name "Net-(IC2B-OUT)") (class "Default")
      (node (ref "IC2") (pin "10") (pinfunction "IN_10") (pintype "bidirectional"))
      (node (ref "IC2") (pin "12") (pinfunction "OUT_12") (pintype "bidirectional"))
      (node (ref "R45") (pin "1") (pinfunction "1_1") (pintype "passive"))
    )
    (net (code "38") (name "Net-(IC2C-OUT)") (class "Default")
      (node (ref "C8") (pin "1") (pinfunction "1_1") (pintype "passive"))
      (node (ref "IC2") (pin "8") (pinfunction "OUT_8") (pintype "bidirectional"))
      (node (ref "R19") (pin "1") (pinfunction "1_1") (pintype "passive"))
    )
    (net (code "39") (name "Net-(IC2D-OUT)") (class "Default")
      (node (ref "C21") (pin "-") (pinfunction "-_-") (pintype "passive"))
      (node (ref "IC2") (pin "9") (pinfunction "OUT_9") (pintype "bidirectional"))
      (node (ref "R46") (pin "1") (pinfunction "1_1") (pintype "passive"))
    )
    (net (code "40") (name "Net-(IC3A-CIN)") (class "Default")
      (node (ref "C18") (pin "2") (pinfunction "2_2") (pintype "passive"))
      (node (ref "D3") (pin "C") (pinfunction "C_C") (pintype "passive"))
      (node (ref "IC3") (pin "3") (pinfunction "CIN_3") (pintype "input"))
      (node (ref "R42") (pin "1") (pinfunction "1_1") (pintype "passive"))
    )
    (net (code "41") (name "Net-(IC3A-R1)") (class "Default")
      (node (ref "IC3") (pin "11") (pinfunction "R1_11") (pintype "input"))
      (node (ref "R48") (pin "1") (pinfunction "1_1") (pintype "passive"))
    )
    (net (code "42") (name "Net-(IC3A-VCOOUT)") (class "Default")
      (node (ref "C20") (pin "2") (pinfunction "2_2") (pintype "passive"))
      (node (ref "IC3") (pin "4") (pinfunction "VCOOUT_4") (pintype "output"))
    )
    (net (code "43") (name "Net-(IC4A-BYPASS)") (class "Default")
      (node (ref "C17") (pin "+") (pinfunction "+_+") (pintype "passive"))
      (node (ref "IC4") (pin "10") (pinfunction "BYPASS_10") (pintype "input"))
    )
    (net (code "44") (name "Net-(IC4A-C1)") (class "Default")
      (node (ref "C15") (pin "1") (pinfunction "1_1") (pintype "passive"))
      (node (ref "IC4") (pin "5") (pinfunction "C1_5") (pintype "input"))
    )
    (net (code "45") (name "Net-(IC4A-C2)") (class "Default")
      (node (ref "C15") (pin "2") (pinfunction "2_2") (pintype "passive"))
      (node (ref "IC4") (pin "6") (pinfunction "C2_6") (pintype "input"))
    )
    (net (code "46") (name "Net-(IC4A-MULT_OUT)") (class "Default")
      (node (ref "IC4") (pin "3") (pinfunction "MULT_OUT_3") (pintype "output"))
      (node (ref "R34") (pin "1") (pinfunction "1_1") (pintype "passive"))
    )
    (net (code "47") (name "Net-(IC4A-R1)") (class "Default")
      (node (ref "IC4") (pin "7") (pinfunction "R1_7") (pintype "input"))
      (node (ref "R37") (pin "1") (pinfunction "1_1") (pintype "passive"))
    )
    (net (code "48") (name "Net-(IC4A-SI{slash}TR)") (class "Default")
      (node (ref "C14") (pin "+") (pinfunction "+_+") (pintype "passive"))
      (node (ref "IC4") (pin "2") (pinfunction "SI/TR_2") (pintype "output"))
    )
    (net (code "49") (name "Net-(IC5A-+IN)") (class "Default")
      (node (ref "IC5") (pin "3") (pinfunction "+IN_3") (pintype "bidirectional"))
      (node (ref "R5") (pin "1") (pinfunction "1_1") (pintype "passive"))
      (node (ref "R6") (pin "2") (pinfunction "2_2") (pintype "passive"))
    )
    (net (code "50") (name "Net-(IC5A-IABC)") (class "Default")
      (node (ref "IC5") (pin "1") (pinfunction "IABC_1") (pintype "bidirectional"))
      (node (ref "IC5") (pin "16") (pinfunction "IABC_16") (pintype "bidirectional"))
      (node (ref "T2") (pin "C") (pinfunction "C_C") (pintype "passive"))
    )
    (net (code "51") (name "Net-(IC5A-OUT)") (class "Default")
      (node (ref "C3") (pin "1") (pinfunction "1_1") (pintype "passive"))
      (node (ref "IC5") (pin "5") (pinfunction "OUT_5") (pintype "bidirectional"))
      (node (ref "IC5") (pin "7") (pinfunction "IN_7") (pintype "bidirectional"))
    )
    (net (code "52") (name "Net-(IC5B-+IN)") (class "Default")
      (node (ref "IC5") (pin "14") (pinfunction "+IN_14") (pintype "bidirectional"))
      (node (ref "R10") (pin "2") (pinfunction "2_2") (pintype "passive"))
      (node (ref "R9") (pin "2") (pinfunction "2_2") (pintype "passive"))
    )
    (net (code "53") (name "Net-(IC5B--IN)") (class "Default")
      (node (ref "IC5") (pin "13") (pinfunction "-IN_13") (pintype "bidirectional"))
      (node (ref "R11") (pin "1") (pinfunction "1_1") (pintype "passive"))
    )
    (net (code "54") (name "Net-(IC5B-OUT)") (class "Default")
      (node (ref "C6") (pin "1") (pinfunction "1_1") (pintype "passive"))
      (node (ref "IC5") (pin "10") (pinfunction "IN_10") (pintype "bidirectional"))
      (node (ref "IC5") (pin "12") (pinfunction "OUT_12") (pintype "bidirectional"))
    )
    (net (code "55") (name "Net-(IC6A-+IN)") (class "Default")
      (node (ref "C9") (pin "1") (pinfunction "1_1") (pintype "passive"))
      (node (ref "D1") (pin "A") (pinfunction "A_A") (pintype "passive"))
      (node (ref "D2") (pin "C") (pinfunction "C_C") (pintype "passive"))
      (node (ref "IC6") (pin "3") (pinfunction "+IN_3") (pintype "bidirectional"))
    )
    (net (code "56") (name "Net-(IC6A--IN)") (class "Default")
      (node (ref "IC6") (pin "4") (pinfunction "-IN_4") (pintype "bidirectional"))
      (node (ref "R20") (pin "1") (pinfunction "1_1") (pintype "passive"))
      (node (ref "R21") (pin "2") (pinfunction "2_2") (pintype "passive"))
    )
    (net (code "57") (name "Net-(IC6A-IABC)") (class "Default")
      (node (ref "IC6") (pin "1") (pinfunction "IABC_1") (pintype "bidirectional"))
      (node (ref "T6") (pin "C") (pinfunction "C_C") (pintype "passive"))
    )
    (net (code "58") (name "Net-(IC6A-OUT)") (class "Default")
      (node (ref "C9") (pin "2") (pinfunction "2_2") (pintype "passive"))
      (node (ref "IC6") (pin "5") (pinfunction "OUT_5") (pintype "bidirectional"))
      (node (ref "IC6") (pin "7") (pinfunction "IN_7") (pintype "bidirectional"))
    )
    (net (code "59") (name "Net-(IC6B-+IN)") (class "Default")
      (node (ref "IC6") (pin "14") (pinfunction "+IN_14") (pintype "bidirectional"))
      (node (ref "R26") (pin "1") (pinfunction "1_1") (pintype "passive"))
      (node (ref "R27") (pin "1") (pinfunction "1_1") (pintype "passive"))
    )
    (net (code "60") (name "Net-(IC6B--IN)") (class "Default")
      (node (ref "IC6") (pin "13") (pinfunction "-IN_13") (pintype "bidirectional"))
      (node (ref "R25") (pin "1") (pinfunction "1_1") (pintype "passive"))
    )
    (net (code "61") (name "Net-(IC6B-IABC)") (class "Default")
      (node (ref "IC6") (pin "16") (pinfunction "IABC_16") (pintype "bidirectional"))
      (node (ref "T7") (pin "C") (pinfunction "C_C") (pintype "passive"))
    )
    (net (code "62") (name "Net-(IC6B-OUT)") (class "Default")
      (node (ref "IC6") (pin "10") (pinfunction "IN_10") (pintype "bidirectional"))
      (node (ref "IC6") (pin "12") (pinfunction "OUT_12") (pintype "bidirectional"))
      (node (ref "R28") (pin "1") (pinfunction "1_1") (pintype "passive"))
    )
    (net (code "63") (name "Net-(IC6C-OUT)") (class "Default")
      (node (ref "C10") (pin "1") (pinfunction "1_1") (pintype "passive"))
      (node (ref "IC6") (pin "8") (pinfunction "OUT_8") (pintype "bidirectional"))
      (node (ref "R21") (pin "1") (pinfunction "1_1") (pintype "passive"))
      (node (ref "R22") (pin "1") (pinfunction "1_1") (pintype "passive"))
    )
    (net (code "64") (name "Net-(IC6D-OUT)") (class "Default")
      (node (ref "C11") (pin "-") (pinfunction "-_-") (pintype "passive"))
      (node (ref "IC6") (pin "9") (pinfunction "OUT_9") (pintype "bidirectional"))
      (node (ref "R29") (pin "1") (pinfunction "1_1") (pintype "passive"))
    )
    (net (code "65") (name "Net-(R2-Pad1)") (class "Default")
      (node (ref "R2") (pin "1") (pinfunction "1_1") (pintype "passive"))
      (node (ref "R4") (pin "2") (pinfunction "2_2") (pintype "passive"))
      (node (ref "T2") (pin "E") (pinfunction "E_E") (pintype "passive"))
    )
    (net (code "66") (name "Net-(R15-Pad1)") (class "Default")
      (node (ref "R15") (pin "1") (pinfunction "1_1") (pintype "passive"))
      (node (ref "T5") (pin "E") (pinfunction "E_E") (pintype "passive"))
    )
    (net (code "67") (name "Net-(R23-Pad1)") (class "Default")
      (node (ref "R23") (pin "1") (pinfunction "1_1") (pintype "passive"))
      (node (ref "T6") (pin "E") (pinfunction "E_E") (pintype "passive"))
    )
    (net (code "68") (name "Net-(R24-Pad2)") (class "Default")
      (node (ref "R24") (pin "2") (pinfunction "2_2") (pintype "passive"))
      (node (ref "T7") (pin "E") (pinfunction "E_E") (pintype "passive"))
    )
    (net (code "69") (name "Net-(R37-Pad2)") (class "Default")
      (node (ref "R37") (pin "2") (pinfunction "2_2") (pintype "passive"))
      (node (ref "T8") (pin "C") (pinfunction "C_C") (pintype "passive"))
    )
    (net (code "70") (name "Net-(R38-Pad2)") (class "Default")
      (node (ref "R38") (pin "2") (pinfunction "2_2") (pintype "passive"))
      (node (ref "T8") (pin "B") (pinfunction "B_B") (pintype "passive"))
      (node (ref "T9") (pin "E") (pinfunction "E_E") (pintype "passive"))
    )
    (net (code "71") (name "Net-(R47-Pad1)") (class "Default")
      (node (ref "R47") (pin "1") (pinfunction "1_1") (pintype "passive"))
      (node (ref "T10") (pin "E") (pinfunction "E_E") (pintype "passive"))
    )
    (net (code "72") (name "Net-(R48-Pad2)") (class "Default")
      (node (ref "R48") (pin "2") (pinfunction "2_2") (pintype "passive"))
      (node (ref "T11") (pin "C") (pinfunction "C_C") (pintype "passive"))
    )
    (net (code "73") (name "Net-(R49-Pad2)") (class "Default")
      (node (ref "R49") (pin "2") (pinfunction "2_2") (pintype "passive"))
      (node (ref "T11") (pin "B") (pinfunction "B_B") (pintype "passive"))
      (node (ref "T12") (pin "E") (pinfunction "E_E") (pintype "passive"))
    )
    (net (code "74") (name "Net-(R50-Pad2)") (class "Default")
      (node (ref "R50") (pin "2") (pinfunction "2_2") (pintype "passive"))
      (node (ref "R51") (pin "1") (pinfunction "1_1") (pintype "passive"))
      (node (ref "R52") (pin "2") (pinfunction "2_2") (pintype "passive"))
      (node (ref "T12") (pin "B") (pinfunction "B_B") (pintype "passive"))
    )
    (net (code "75") (name "Net-(T3-PadB)") (class "Default")
      (node (ref "T3") (pin "B") (pinfunction "B_B") (pintype "passive"))
      (node (ref "T4") (pin "B") (pinfunction "B_B") (pintype "passive"))
    )
    (net (code "76") (name "RINGMOD_BALANCE") (class "Default")
      (node (ref "R31") (pin "2") (pinfunction "2_2") (pintype "passive"))
      (node (ref "RINGMOD") (pin "1") (pinfunction "1_1") (pintype "passive"))
    )
    (net (code "77") (name "RINGMOD_DEPTH_A") (class "Default")
      (node (ref "C10") (pin "2") (pinfunction "2_2") (pintype "passive"))
      (node (ref "RINGMOD") (pin "3") (pinfunction "3_3") (pintype "passive"))
    )
    (net (code "78") (name "RINGMOD_DEPTH_B") (class "Default")
      (node (ref "R30") (pin "1") (pinfunction "1_1") (pintype "passive"))
      (node (ref "RINGMOD") (pin "4") (pinfunction "4_4") (pintype "passive"))
    )
    (net (code "79") (name "RINGMOD_FREQ") (class "Default")
      (node (ref "R23") (pin "2") (pinfunction "2_2") (pintype "passive"))
      (node (ref "RINGMOD") (pin "2") (pinfunction "2_2") (pintype "passive"))
    )
    (net (code "80") (name "SHELL_A") (class "Default")
      (node (ref "R24") (pin "1") (pinfunction "1_1") (pintype "passive"))
      (node (ref "SHELL_OUT") (pin "4") (pinfunction "4_4") (pintype "passive"))
    )
    (net (code "81") (name "SHELL_COMB") (class "Default")
      (node (ref "R39") (pin "1") (pinfunction "1_1") (pintype "passive"))
      (node (ref "SHELL_OUT") (pin "5") (pinfunction "5_5") (pintype "passive"))
      (node (ref "T9") (pin "B") (pinfunction "B_B") (pintype "passive"))
    )
    (net (code "82") (name "SHELL_OUTPUT") (class "Default")
      (node (ref "C11") (pin "+") (pinfunction "+_+") (pintype "passive"))
      (node (ref "SHELL_OUT") (pin "1") (pinfunction "1_1") (pintype "passive"))
    )
    (net (code "83") (name "STATUS_LED") (class "Default")
      (node (ref "IC3") (pin "2") (pinfunction "PC1_2") (pintype "output"))
    )
    (net (code "84") (name "unconnected-(IC2A-ID-Pad2)") (class "Default")
      (node (ref "IC2") (pin "2") (pinfunction "ID_2") (pintype "bidirectional"))
    )
    (net (code "85") (name "unconnected-(IC2B-ID-Pad15)") (class "Default")
      (node (ref "IC2") (pin "15") (pinfunction "ID_15") (pintype "bidirectional"))
    )
    (net (code "86") (name "unconnected-(IC3A-DEMO-Pad10)") (class "Default")
      (node (ref "IC3") (pin "10") (pinfunction "DEMO_10") (pintype "output"))
    )
    (net (code "87") (name "unconnected-(IC3A-PC2-Pad13)") (class "Default")
      (node (ref "IC3") (pin "13") (pinfunction "PC2_13") (pintype "output"))
    )
    (net (code "88") (name "unconnected-(IC3A-PP-Pad1)") (class "Default")
      (node (ref "IC3") (pin "1") (pinfunction "PP_1") (pintype "output"))
    )
    (net (code "89") (name "unconnected-(IC3A-R2-Pad12)") (class "Default")
      (node (ref "IC3") (pin "12") (pinfunction "R2_12") (pintype "input"))
    )
    (net (code "90") (name "unconnected-(IC3A-ZEN-Pad15)") (class "Default")
      (node (ref "IC3") (pin "15") (pinfunction "ZEN_15") (pintype "input"))
    )
    (net (code "91") (name "unconnected-(IC4A-FSK_IN-Pad9)") (class "Default")
      (node (ref "IC4") (pin "9") (pinfunction "FSK_IN_9") (pintype "input"))
    )
    (net (code "92") (name "unconnected-(IC4A-R2-Pad8)") (class "Default")
      (node (ref "IC4") (pin "8") (pinfunction "R2_8") (pintype "input"))
    )
    (net (code "93") (name "unconnected-(IC4A-SYNC-Pad11)") (class "Default")
      (node (ref "IC4") (pin "11") (pinfunction "SYNC_11") (pintype "output"))
    )
    (net (code "94") (name "unconnected-(IC4A-S_ADJ-Pad15)") (class "Default")
      (node (ref "IC4") (pin "15") (pinfunction "S_ADJ_15") (pintype "input"))
    )
    (net (code "95") (name "unconnected-(IC4A-S_ADJ-Pad16)") (class "Default")
      (node (ref "IC4") (pin "16") (pinfunction "S_ADJ_16") (pintype "input"))
    )
    (net (code "96") (name "unconnected-(IC4A-W_ADJ-Pad13)") (class "Default")
      (node (ref "IC4") (pin "13") (pinfunction "W_ADJ_13") (pintype "input"))
    )
    (net (code "97") (name "unconnected-(IC4A-W_ADJ-Pad14)") (class "Default")
      (node (ref "IC4") (pin "14") (pinfunction "W_ADJ_14") (pintype "input"))
    )
    (net (code "98") (name "unconnected-(IC5A-ID-Pad2)") (class "Default")
      (node (ref "IC5") (pin "2") (pinfunction "ID_2") (pintype "bidirectional"))
    )
    (net (code "99") (name "unconnected-(IC5B-ID-Pad15)") (class "Default")
      (node (ref "IC5") (pin "15") (pinfunction "ID_15") (pintype "bidirectional"))
    )
    (net (code "100") (name "unconnected-(IC6A-ID-Pad2)") (class "Default")
      (node (ref "IC6") (pin "2") (pinfunction "ID_2") (pintype "bidirectional"))
    )
    (net (code "101") (name "unconnected-(IC6B-ID-Pad15)") (class "Default")
      (node (ref "IC6") (pin "15") (pinfunction "ID_15") (pintype "bidirectional"))
    )
    (net (code "102") (name "unconnected-(T4-PadC)") (class "Default")
      (node (ref "T4") (pin "C") (pinfunction "C_C") (pintype "passive"))
    )
  )
)
